# Con_midi_din5.net
KiCad netlist of a schematic drawn in Altium Designer
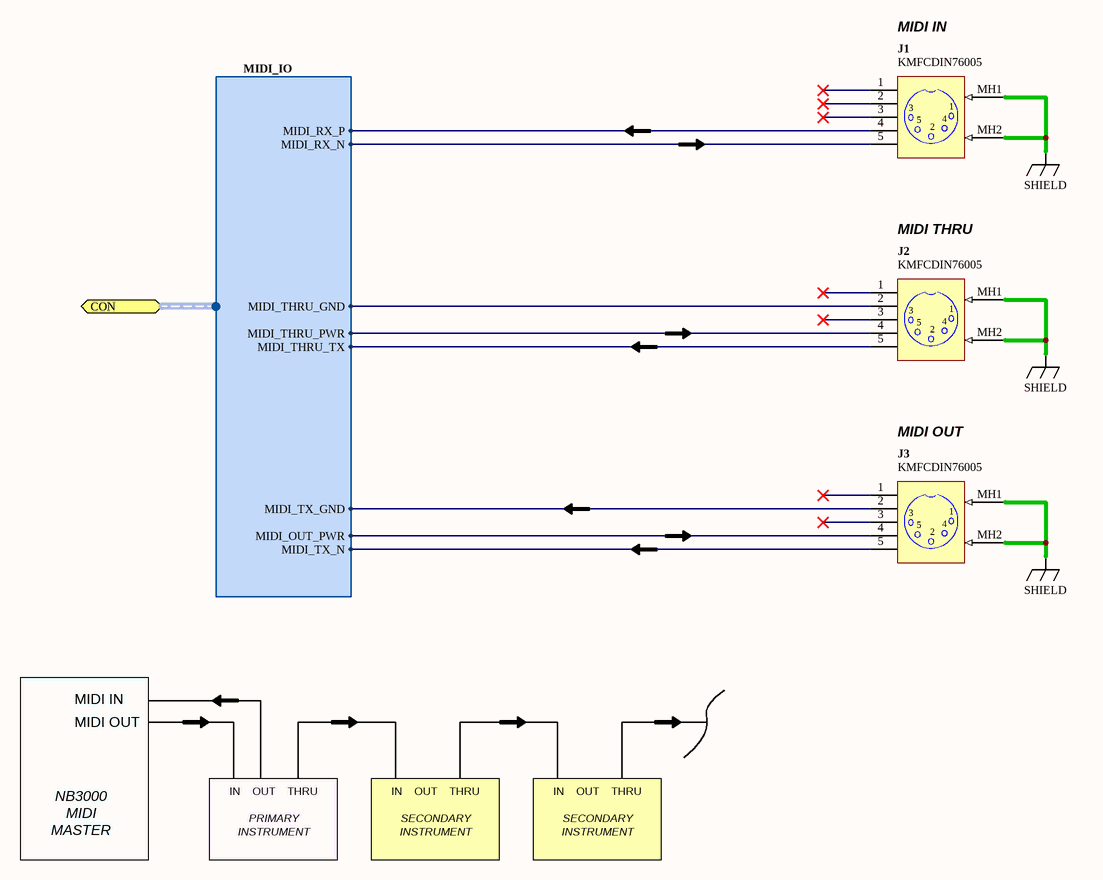
[diagram p0: Con_midi_din5.schdoc]

(export (version "E")
  (design (tool "Eeschema 10.0.6"))
  (components
    (comp (ref "J1")
      (value "KMFCDIN76005")
      (footprint "KMFCDIN76005")
      (description "Socket, 5-way R/A DIN")
      (libsource (lib "AltiumDesignLibrary") (part "KMFCDIN76005"))
    )
    (comp (ref "J2")
      (value "KMFCDIN76005")
      (footprint "KMFCDIN76005")
      (description "Socket, 5-way R/A DIN")
      (libsource (lib "AltiumDesignLibrary") (part "KMFCDIN76005"))
    )
    (comp (ref "J3")
      (value "KMFCDIN76005")
      (footprint "KMFCDIN76005")
      (description "Socket, 5-way R/A DIN")
      (libsource (lib "AltiumDesignLibrary") (part "KMFCDIN76005"))
    )
  )
  (nets
    (net (code "2") (name "/MIDI_OUT_PWR") (class "Default")
      (node (ref "J3") (pin "4") (pinfunction "4_4") (pintype "passive"))
    )
    (net (code "3") (name "/MIDI_RX_N") (class "Default")
      (node (ref "J1") (pin "5") (pinfunction "5_5") (pintype "passive"))
    )
    (net (code "4") (name "/MIDI_RX_P") (class "Default")
      (node (ref "J1") (pin "4") (pinfunction "4_4") (pintype "passive"))
    )
    (net (code "5") (name "/MIDI_THRU_GND") (class "Default")
      (node (ref "J2") (pin "2") (pinfunction "2_2") (pintype "passive"))
    )
    (net (code "6") (name "/MIDI_THRU_PWR") (class "Default")
      (node (ref "J2") (pin "4") (pinfunction "4_4") (pintype "passive"))
    )
    (net (code "7") (name "/MIDI_THRU_TX") (class "Default")
      (node (ref "J2") (pin "5") (pinfunction "5_5") (pintype "passive"))
    )
    (net (code "8") (name "/MIDI_TX_GND") (class "Default")
      (node (ref "J3") (pin "2") (pinfunction "2_2") (pintype "passive"))
    )
    (net (code "9") (name "/MIDI_TX_N") (class "Default")
      (node (ref "J3") (pin "5") (pinfunction "5_5") (pintype "passive"))
    )
    (net (code "11") (name "SHIELD") (class "Default")
      (node (ref "J1") (pin "MH1") (pinfunction "MH1_MH1") (pintype "input"))
      (node (ref "J1") (pin "MH2") (pinfunction "MH2_MH2") (pintype "input"))
      (node (ref "J2") (pin "MH1") (pinfunction "MH1_MH1") (pintype "input"))
      (node (ref "J2") (pin "MH2") (pinfunction "MH2_MH2") (pintype "input"))
      (node (ref "J3") (pin "MH1") (pinfunction "MH1_MH1") (pintype "input"))
      (node (ref "J3") (pin "MH2") (pinfunction "MH2_MH2") (pintype "input"))
    )
    (net (code "12") (name "unconnected-(J1-Pad1)") (class "Default")
      (node (ref "J1") (pin "1") (pinfunction "1_1") (pintype "passive+no_connect"))
    )
    (net (code "13") (name "unconnected-(J1-Pad2)") (class "Default")
      (node (ref "J1") (pin "2") (pinfunction "2_2") (pintype "passive+no_connect"))
    )
    (net (code "14") (name "unconnected-(J1-Pad3)") (class "Default")
      (node (ref "J1") (pin "3") (pinfunction "3_3") (pintype "passive+no_connect"))
    )
    (net (code "15") (name "unconnected-(J2-Pad1)") (class "Default")
      (node (ref "J2") (pin "1") (pinfunction "1_1") (pintype "passive+no_connect"))
    )
    (net (code "16") (name "unconnected-(J2-Pad3)") (class "Default")
      (node (ref "J2") (pin "3") (pinfunction "3_3") (pintype "passive+no_connect"))
    )
    (net (code "17") (name "unconnected-(J3-Pad1)") (class "Default")
      (node (ref "J3") (pin "1") (pinfunction "1_1") (pintype "passive+no_connect"))
    )
    (net (code "18") (name "unconnected-(J3-Pad3)") (class "Default")
      (node (ref "J3") (pin "3") (pinfunction "3_3") (pintype "passive+no_connect"))
    )
  )
)
